# XMICRO-BREAKOUT-CARD.net
KiCad netlist of a schematic drawn in EAGLE
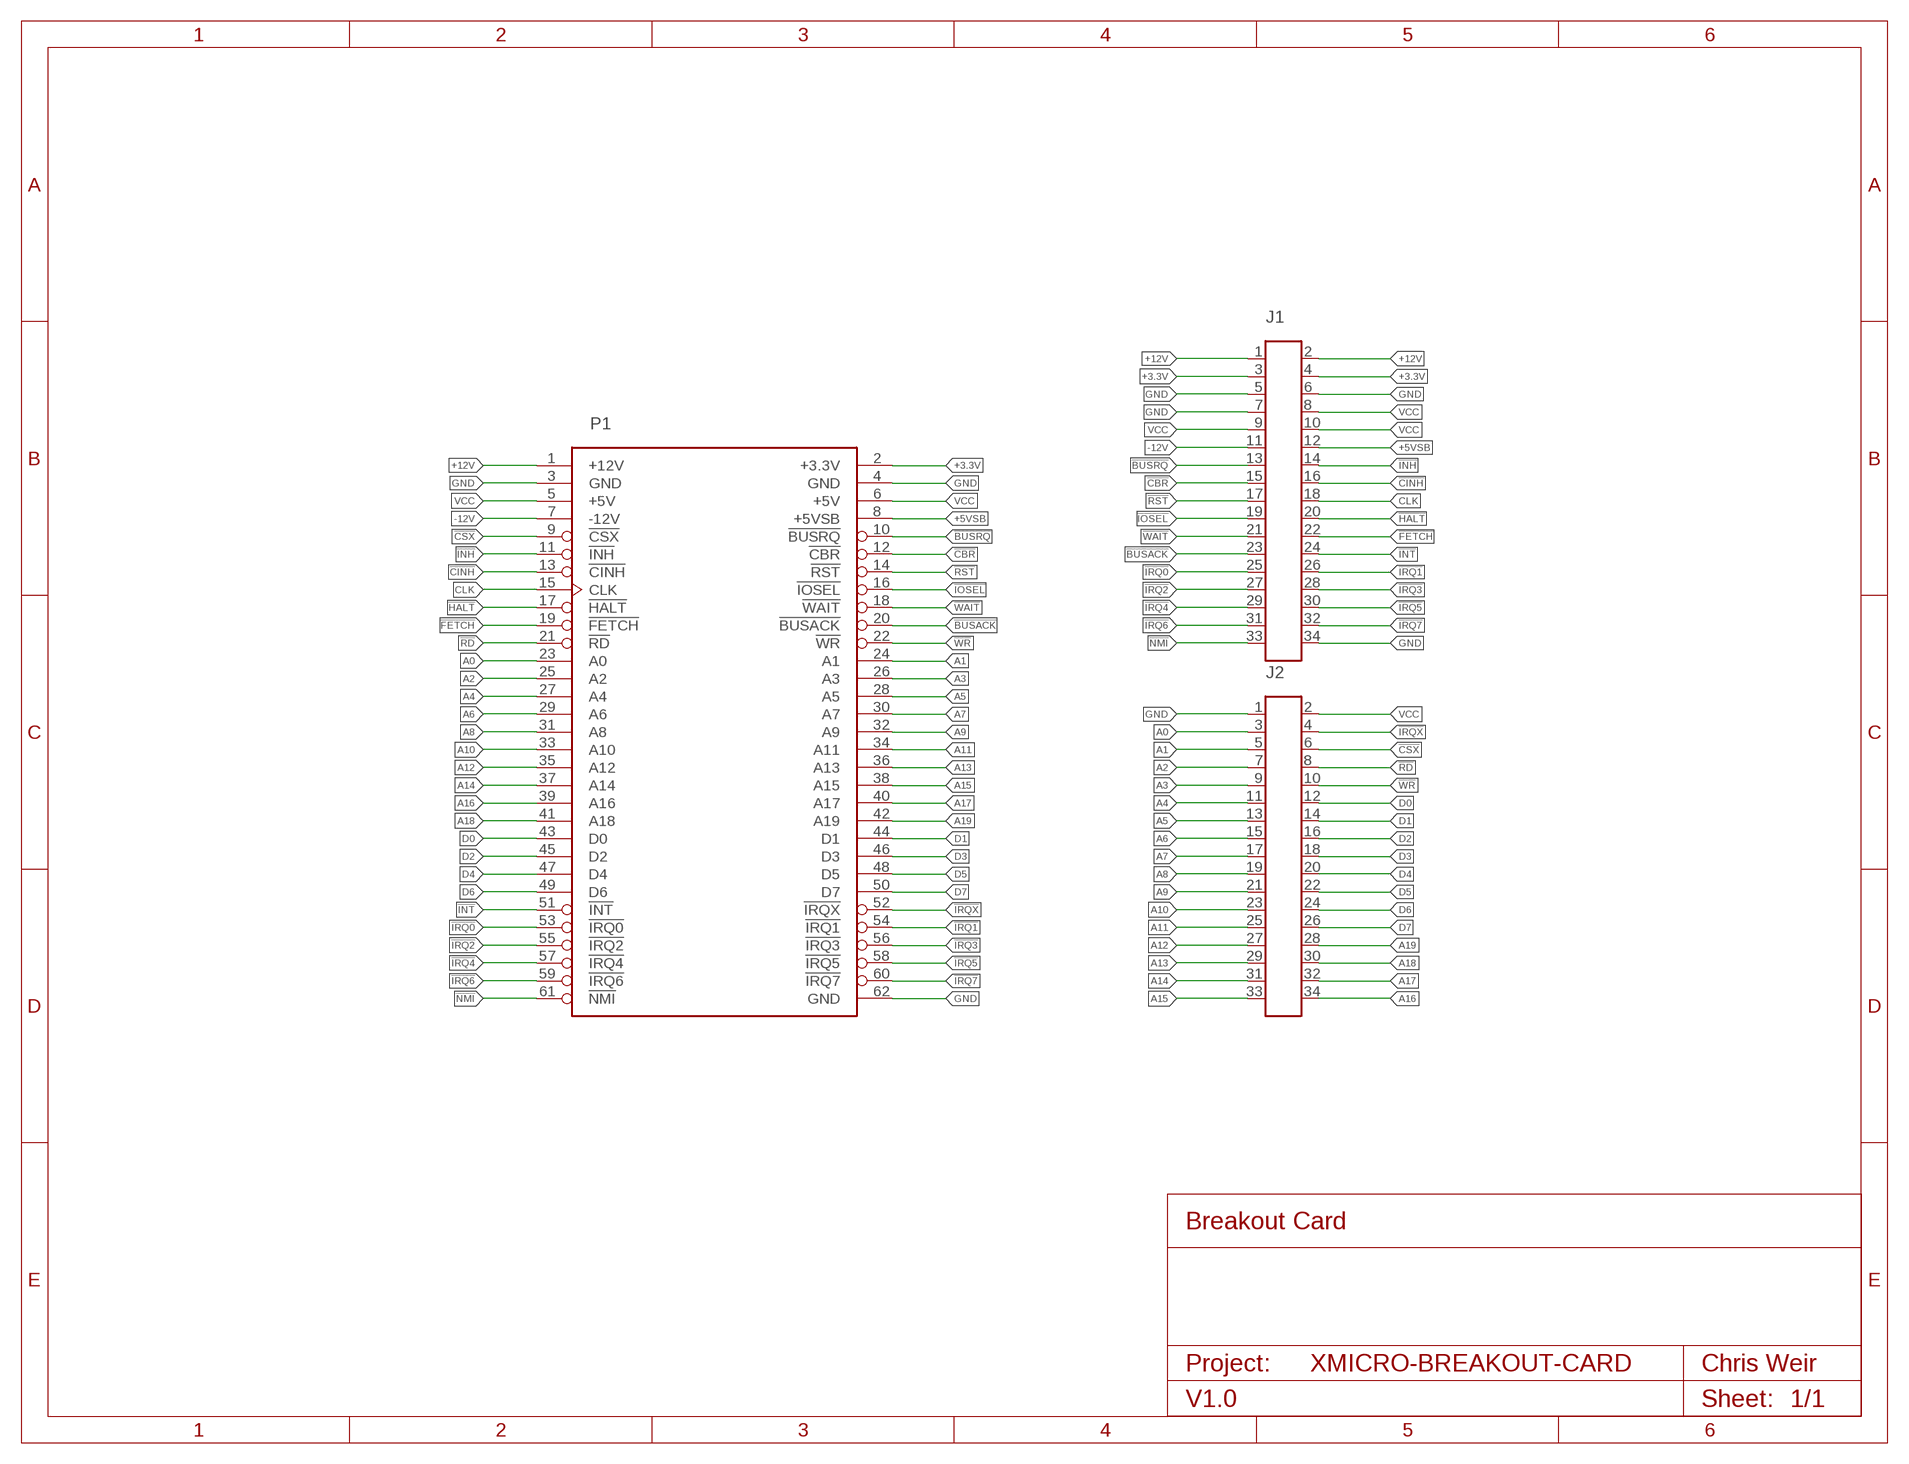
[diagram p0: schematic, sheet 1]

(export (version "E")
  (design (tool "Eeschema 10.0.6"))
  (components
    (comp (ref "J1")
      (value "HDR-17X2")
      (footprint "eagle-import:HDR-17X2S")
      (libsource (lib "eagle-import") (part "HDR-17X2"))
    )
    (comp (ref "J2")
      (value "HDR-17X2")
      (footprint "eagle-import:HDR-17X2S")
      (libsource (lib "eagle-import") (part "HDR-17X2"))
    )
    (comp (ref "P1")
      (value "XMICRO-BUS-PHYSICAL-EDGE62M")
      (footprint "eagle-import:EDGE62M")
      (libsource (lib "eagle-import") (part "XMICRO-BUS-PHYSICAL-EDGE62M"))
    )
  )
  (nets
    (net (code "1") (name "+3.3V") (class "Default")
      (node (ref "J1") (pin "3") (pinfunction "3_3") (pintype "bidirectional"))
      (node (ref "J1") (pin "4") (pinfunction "4_4") (pintype "bidirectional"))
      (node (ref "P1") (pin "2") (pinfunction "+3.3V_2") (pintype "bidirectional"))
    )
    (net (code "2") (name "+5VSB") (class "Default")
      (node (ref "J1") (pin "12") (pinfunction "12_12") (pintype "bidirectional"))
      (node (ref "P1") (pin "8") (pinfunction "+5VSB_8") (pintype "bidirectional"))
    )
    (net (code "3") (name "+12V") (class "Default")
      (node (ref "J1") (pin "1") (pinfunction "1_1") (pintype "bidirectional"))
      (node (ref "J1") (pin "2") (pinfunction "2_2") (pintype "bidirectional"))
      (node (ref "P1") (pin "1") (pinfunction "+12V_1") (pintype "bidirectional"))
    )
    (net (code "4") (name "-12V") (class "Default")
      (node (ref "J1") (pin "11") (pinfunction "11_11") (pintype "bidirectional"))
      (node (ref "P1") (pin "7") (pinfunction "-12V_7") (pintype "bidirectional"))
    )
    (net (code "5") (name "/~{BUSACK}") (class "Default")
      (node (ref "J1") (pin "23") (pinfunction "23_23") (pintype "bidirectional"))
      (node (ref "P1") (pin "20") (pinfunction "~{BUSACK}_20") (pintype "bidirectional"))
    )
    (net (code "6") (name "/~{BUSRQ}") (class "Default")
      (node (ref "J1") (pin "13") (pinfunction "13_13") (pintype "bidirectional"))
      (node (ref "P1") (pin "10") (pinfunction "~{BUSRQ}_10") (pintype "bidirectional"))
    )
    (net (code "7") (name "/~{CBR}") (class "Default")
      (node (ref "J1") (pin "15") (pinfunction "15_15") (pintype "bidirectional"))
      (node (ref "P1") (pin "12") (pinfunction "~{CBR}_12") (pintype "bidirectional"))
    )
    (net (code "8") (name "/~{CINH}") (class "Default")
      (node (ref "J1") (pin "16") (pinfunction "16_16") (pintype "bidirectional"))
      (node (ref "P1") (pin "13") (pinfunction "~{CINH}_13") (pintype "bidirectional"))
    )
    (net (code "9") (name "/~{CSX}") (class "Default")
      (node (ref "J2") (pin "6") (pinfunction "6_6") (pintype "bidirectional"))
      (node (ref "P1") (pin "9") (pinfunction "~{CSX}_9") (pintype "bidirectional"))
    )
    (net (code "10") (name "/~{FETCH}") (class "Default")
      (node (ref "J1") (pin "22") (pinfunction "22_22") (pintype "bidirectional"))
      (node (ref "P1") (pin "19") (pinfunction "~{FETCH}_19") (pintype "bidirectional"))
    )
    (net (code "11") (name "/~{HALT}") (class "Default")
      (node (ref "J1") (pin "20") (pinfunction "20_20") (pintype "bidirectional"))
      (node (ref "P1") (pin "17") (pinfunction "~{HALT}_17") (pintype "bidirectional"))
    )
    (net (code "12") (name "/~{INH}") (class "Default")
      (node (ref "J1") (pin "14") (pinfunction "14_14") (pintype "bidirectional"))
      (node (ref "P1") (pin "11") (pinfunction "~{INH}_11") (pintype "bidirectional"))
    )
    (net (code "13") (name "/~{INT}") (class "Default")
      (node (ref "J1") (pin "24") (pinfunction "24_24") (pintype "bidirectional"))
      (node (ref "P1") (pin "51") (pinfunction "~{INT}_51") (pintype "bidirectional"))
    )
    (net (code "14") (name "/~{IOSEL}") (class "Default")
      (node (ref "J1") (pin "19") (pinfunction "19_19") (pintype "bidirectional"))
      (node (ref "P1") (pin "16") (pinfunction "~{IOSEL}_16") (pintype "bidirectional"))
    )
    (net (code "15") (name "/~{IRQ0}") (class "Default")
      (node (ref "J1") (pin "25") (pinfunction "25_25") (pintype "bidirectional"))
      (node (ref "P1") (pin "53") (pinfunction "~{IRQ0}_53") (pintype "bidirectional"))
    )
    (net (code "16") (name "/~{IRQ1}") (class "Default")
      (node (ref "J1") (pin "26") (pinfunction "26_26") (pintype "bidirectional"))
      (node (ref "P1") (pin "54") (pinfunction "~{IRQ1}_54") (pintype "bidirectional"))
    )
    (net (code "17") (name "/~{IRQ2}") (class "Default")
      (node (ref "J1") (pin "27") (pinfunction "27_27") (pintype "bidirectional"))
      (node (ref "P1") (pin "55") (pinfunction "~{IRQ2}_55") (pintype "bidirectional"))
    )
    (net (code "18") (name "/~{IRQ3}") (class "Default")
      (node (ref "J1") (pin "28") (pinfunction "28_28") (pintype "bidirectional"))
      (node (ref "P1") (pin "56") (pinfunction "~{IRQ3}_56") (pintype "bidirectional"))
    )
    (net (code "19") (name "/~{IRQ4}") (class "Default")
      (node (ref "J1") (pin "29") (pinfunction "29_29") (pintype "bidirectional"))
      (node (ref "P1") (pin "57") (pinfunction "~{IRQ4}_57") (pintype "bidirectional"))
    )
    (net (code "20") (name "/~{IRQ5}") (class "Default")
      (node (ref "J1") (pin "30") (pinfunction "30_30") (pintype "bidirectional"))
      (node (ref "P1") (pin "58") (pinfunction "~{IRQ5}_58") (pintype "bidirectional"))
    )
    (net (code "21") (name "/~{IRQ6}") (class "Default")
      (node (ref "J1") (pin "31") (pinfunction "31_31") (pintype "bidirectional"))
      (node (ref "P1") (pin "59") (pinfunction "~{IRQ6}_59") (pintype "bidirectional"))
    )
    (net (code "22") (name "/~{IRQ7}") (class "Default")
      (node (ref "J1") (pin "32") (pinfunction "32_32") (pintype "bidirectional"))
      (node (ref "P1") (pin "60") (pinfunction "~{IRQ7}_60") (pintype "bidirectional"))
    )
    (net (code "23") (name "/~{IRQX}") (class "Default")
      (node (ref "J2") (pin "4") (pinfunction "4_4") (pintype "bidirectional"))
      (node (ref "P1") (pin "52") (pinfunction "~{IRQX}_52") (pintype "bidirectional"))
    )
    (net (code "24") (name "/~{NMI}") (class "Default")
      (node (ref "J1") (pin "33") (pinfunction "33_33") (pintype "bidirectional"))
      (node (ref "P1") (pin "61") (pinfunction "~{NMI}_61") (pintype "bidirectional"))
    )
    (net (code "25") (name "/~{RD}") (class "Default")
      (node (ref "J2") (pin "8") (pinfunction "8_8") (pintype "bidirectional"))
      (node (ref "P1") (pin "21") (pinfunction "~{RD}_21") (pintype "bidirectional"))
    )
    (net (code "26") (name "/~{RST}") (class "Default")
      (node (ref "J1") (pin "17") (pinfunction "17_17") (pintype "bidirectional"))
      (node (ref "P1") (pin "14") (pinfunction "~{RST}_14") (pintype "bidirectional"))
    )
    (net (code "27") (name "/~{WAIT}") (class "Default")
      (node (ref "J1") (pin "21") (pinfunction "21_21") (pintype "bidirectional"))
      (node (ref "P1") (pin "18") (pinfunction "~{WAIT}_18") (pintype "bidirectional"))
    )
    (net (code "28") (name "/~{WR}") (class "Default")
      (node (ref "J2") (pin "10") (pinfunction "10_10") (pintype "bidirectional"))
      (node (ref "P1") (pin "22") (pinfunction "~{WR}_22") (pintype "bidirectional"))
    )
    (net (code "29") (name "A0") (class "Default")
      (node (ref "J2") (pin "3") (pinfunction "3_3") (pintype "bidirectional"))
      (node (ref "P1") (pin "23") (pinfunction "A0_23") (pintype "bidirectional"))
    )
    (net (code "30") (name "A1") (class "Default")
      (node (ref "J2") (pin "5") (pinfunction "5_5") (pintype "bidirectional"))
      (node (ref "P1") (pin "24") (pinfunction "A1_24") (pintype "bidirectional"))
    )
    (net (code "31") (name "A2") (class "Default")
      (node (ref "J2") (pin "7") (pinfunction "7_7") (pintype "bidirectional"))
      (node (ref "P1") (pin "25") (pinfunction "A2_25") (pintype "bidirectional"))
    )
    (net (code "32") (name "A3") (class "Default")
      (node (ref "J2") (pin "9") (pinfunction "9_9") (pintype "bidirectional"))
      (node (ref "P1") (pin "26") (pinfunction "A3_26") (pintype "bidirectional"))
    )
    (net (code "33") (name "A4") (class "Default")
      (node (ref "J2") (pin "11") (pinfunction "11_11") (pintype "bidirectional"))
      (node (ref "P1") (pin "27") (pinfunction "A4_27") (pintype "bidirectional"))
    )
    (net (code "34") (name "A5") (class "Default")
      (node (ref "J2") (pin "13") (pinfunction "13_13") (pintype "bidirectional"))
      (node (ref "P1") (pin "28") (pinfunction "A5_28") (pintype "bidirectional"))
    )
    (net (code "35") (name "A6") (class "Default")
      (node (ref "J2") (pin "15") (pinfunction "15_15") (pintype "bidirectional"))
      (node (ref "P1") (pin "29") (pinfunction "A6_29") (pintype "bidirectional"))
    )
    (net (code "36") (name "A7") (class "Default")
      (node (ref "J2") (pin "17") (pinfunction "17_17") (pintype "bidirectional"))
      (node (ref "P1") (pin "30") (pinfunction "A7_30") (pintype "bidirectional"))
    )
    (net (code "37") (name "A8") (class "Default")
      (node (ref "J2") (pin "19") (pinfunction "19_19") (pintype "bidirectional"))
      (node (ref "P1") (pin "31") (pinfunction "A8_31") (pintype "bidirectional"))
    )
    (net (code "38") (name "A9") (class "Default")
      (node (ref "J2") (pin "21") (pinfunction "21_21") (pintype "bidirectional"))
      (node (ref "P1") (pin "32") (pinfunction "A9_32") (pintype "bidirectional"))
    )
    (net (code "39") (name "A10") (class "Default")
      (node (ref "J2") (pin "23") (pinfunction "23_23") (pintype "bidirectional"))
      (node (ref "P1") (pin "33") (pinfunction "A10_33") (pintype "bidirectional"))
    )
    (net (code "40") (name "A11") (class "Default")
      (node (ref "J2") (pin "25") (pinfunction "25_25") (pintype "bidirectional"))
      (node (ref "P1") (pin "34") (pinfunction "A11_34") (pintype "bidirectional"))
    )
    (net (code "41") (name "A12") (class "Default")
      (node (ref "J2") (pin "27") (pinfunction "27_27") (pintype "bidirectional"))
      (node (ref "P1") (pin "35") (pinfunction "A12_35") (pintype "bidirectional"))
    )
    (net (code "42") (name "A13") (class "Default")
      (node (ref "J2") (pin "29") (pinfunction "29_29") (pintype "bidirectional"))
      (node (ref "P1") (pin "36") (pinfunction "A13_36") (pintype "bidirectional"))
    )
    (net (code "43") (name "A14") (class "Default")
      (node (ref "J2") (pin "31") (pinfunction "31_31") (pintype "bidirectional"))
      (node (ref "P1") (pin "37") (pinfunction "A14_37") (pintype "bidirectional"))
    )
    (net (code "44") (name "A15") (class "Default")
      (node (ref "J2") (pin "33") (pinfunction "33_33") (pintype "bidirectional"))
      (node (ref "P1") (pin "38") (pinfunction "A15_38") (pintype "bidirectional"))
    )
    (net (code "45") (name "A16") (class "Default")
      (node (ref "J2") (pin "34") (pinfunction "34_34") (pintype "bidirectional"))
      (node (ref "P1") (pin "39") (pinfunction "A16_39") (pintype "bidirectional"))
    )
    (net (code "46") (name "A17") (class "Default")
      (node (ref "J2") (pin "32") (pinfunction "32_32") (pintype "bidirectional"))
      (node (ref "P1") (pin "40") (pinfunction "A17_40") (pintype "bidirectional"))
    )
    (net (code "47") (name "A18") (class "Default")
      (node (ref "J2") (pin "30") (pinfunction "30_30") (pintype "bidirectional"))
      (node (ref "P1") (pin "41") (pinfunction "A18_41") (pintype "bidirectional"))
    )
    (net (code "48") (name "A19") (class "Default")
      (node (ref "J2") (pin "28") (pinfunction "28_28") (pintype "bidirectional"))
      (node (ref "P1") (pin "42") (pinfunction "A19_42") (pintype "bidirectional"))
    )
    (net (code "49") (name "CLK") (class "Default")
      (node (ref "J1") (pin "18") (pinfunction "18_18") (pintype "bidirectional"))
      (node (ref "P1") (pin "15") (pinfunction "CLK_15") (pintype "bidirectional"))
    )
    (net (code "50") (name "D0") (class "Default")
      (node (ref "J2") (pin "12") (pinfunction "12_12") (pintype "bidirectional"))
      (node (ref "P1") (pin "43") (pinfunction "D0_43") (pintype "bidirectional"))
    )
    (net (code "51") (name "D1") (class "Default")
      (node (ref "J2") (pin "14") (pinfunction "14_14") (pintype "bidirectional"))
      (node (ref "P1") (pin "44") (pinfunction "D1_44") (pintype "bidirectional"))
    )
    (net (code "52") (name "D2") (class "Default")
      (node (ref "J2") (pin "16") (pinfunction "16_16") (pintype "bidirectional"))
      (node (ref "P1") (pin "45") (pinfunction "D2_45") (pintype "bidirectional"))
    )
    (net (code "53") (name "D3") (class "Default")
      (node (ref "J2") (pin "18") (pinfunction "18_18") (pintype "bidirectional"))
      (node (ref "P1") (pin "46") (pinfunction "D3_46") (pintype "bidirectional"))
    )
    (net (code "54") (name "D4") (class "Default")
      (node (ref "J2") (pin "20") (pinfunction "20_20") (pintype "bidirectional"))
      (node (ref "P1") (pin "47") (pinfunction "D4_47") (pintype "bidirectional"))
    )
    (net (code "55") (name "D5") (class "Default")
      (node (ref "J2") (pin "22") (pinfunction "22_22") (pintype "bidirectional"))
      (node (ref "P1") (pin "48") (pinfunction "D5_48") (pintype "bidirectional"))
    )
    (net (code "56") (name "D6") (class "Default")
      (node (ref "J2") (pin "24") (pinfunction "24_24") (pintype "bidirectional"))
      (node (ref "P1") (pin "49") (pinfunction "D6_49") (pintype "bidirectional"))
    )
    (net (code "57") (name "D7") (class "Default")
      (node (ref "J2") (pin "26") (pinfunction "26_26") (pintype "bidirectional"))
      (node (ref "P1") (pin "50") (pinfunction "D7_50") (pintype "bidirectional"))
    )
    (net (code "58") (name "GND") (class "Default")
      (node (ref "J1") (pin "34") (pinfunction "34_34") (pintype "bidirectional"))
      (node (ref "J1") (pin "5") (pinfunction "5_5") (pintype "bidirectional"))
      (node (ref "J1") (pin "6") (pinfunction "6_6") (pintype "bidirectional"))
      (node (ref "J1") (pin "7") (pinfunction "7_7") (pintype "bidirectional"))
      (node (ref "J2") (pin "1") (pinfunction "1_1") (pintype "bidirectional"))
      (node (ref "P1") (pin "3") (pinfunction "GND_3") (pintype "bidirectional"))
      (node (ref "P1") (pin "4") (pinfunction "GND_4") (pintype "bidirectional"))
      (node (ref "P1") (pin "62") (pinfunction "GND_62") (pintype "bidirectional"))
    )
    (net (code "59") (name "VCC") (class "Default")
      (node (ref "J1") (pin "10") (pinfunction "10_10") (pintype "bidirectional"))
      (node (ref "J1") (pin "8") (pinfunction "8_8") (pintype "bidirectional"))
      (node (ref "J1") (pin "9") (pinfunction "9_9") (pintype "bidirectional"))
      (node (ref "J2") (pin "2") (pinfunction "2_2") (pintype "bidirectional"))
      (node (ref "P1") (pin "5") (pinfunction "+5V_5") (pintype "bidirectional"))
      (node (ref "P1") (pin "6") (pinfunction "+5V_6") (pintype "bidirectional"))
    )
  )
)
